# QT2640.net
KiCad netlist of a schematic drawn in EAGLE
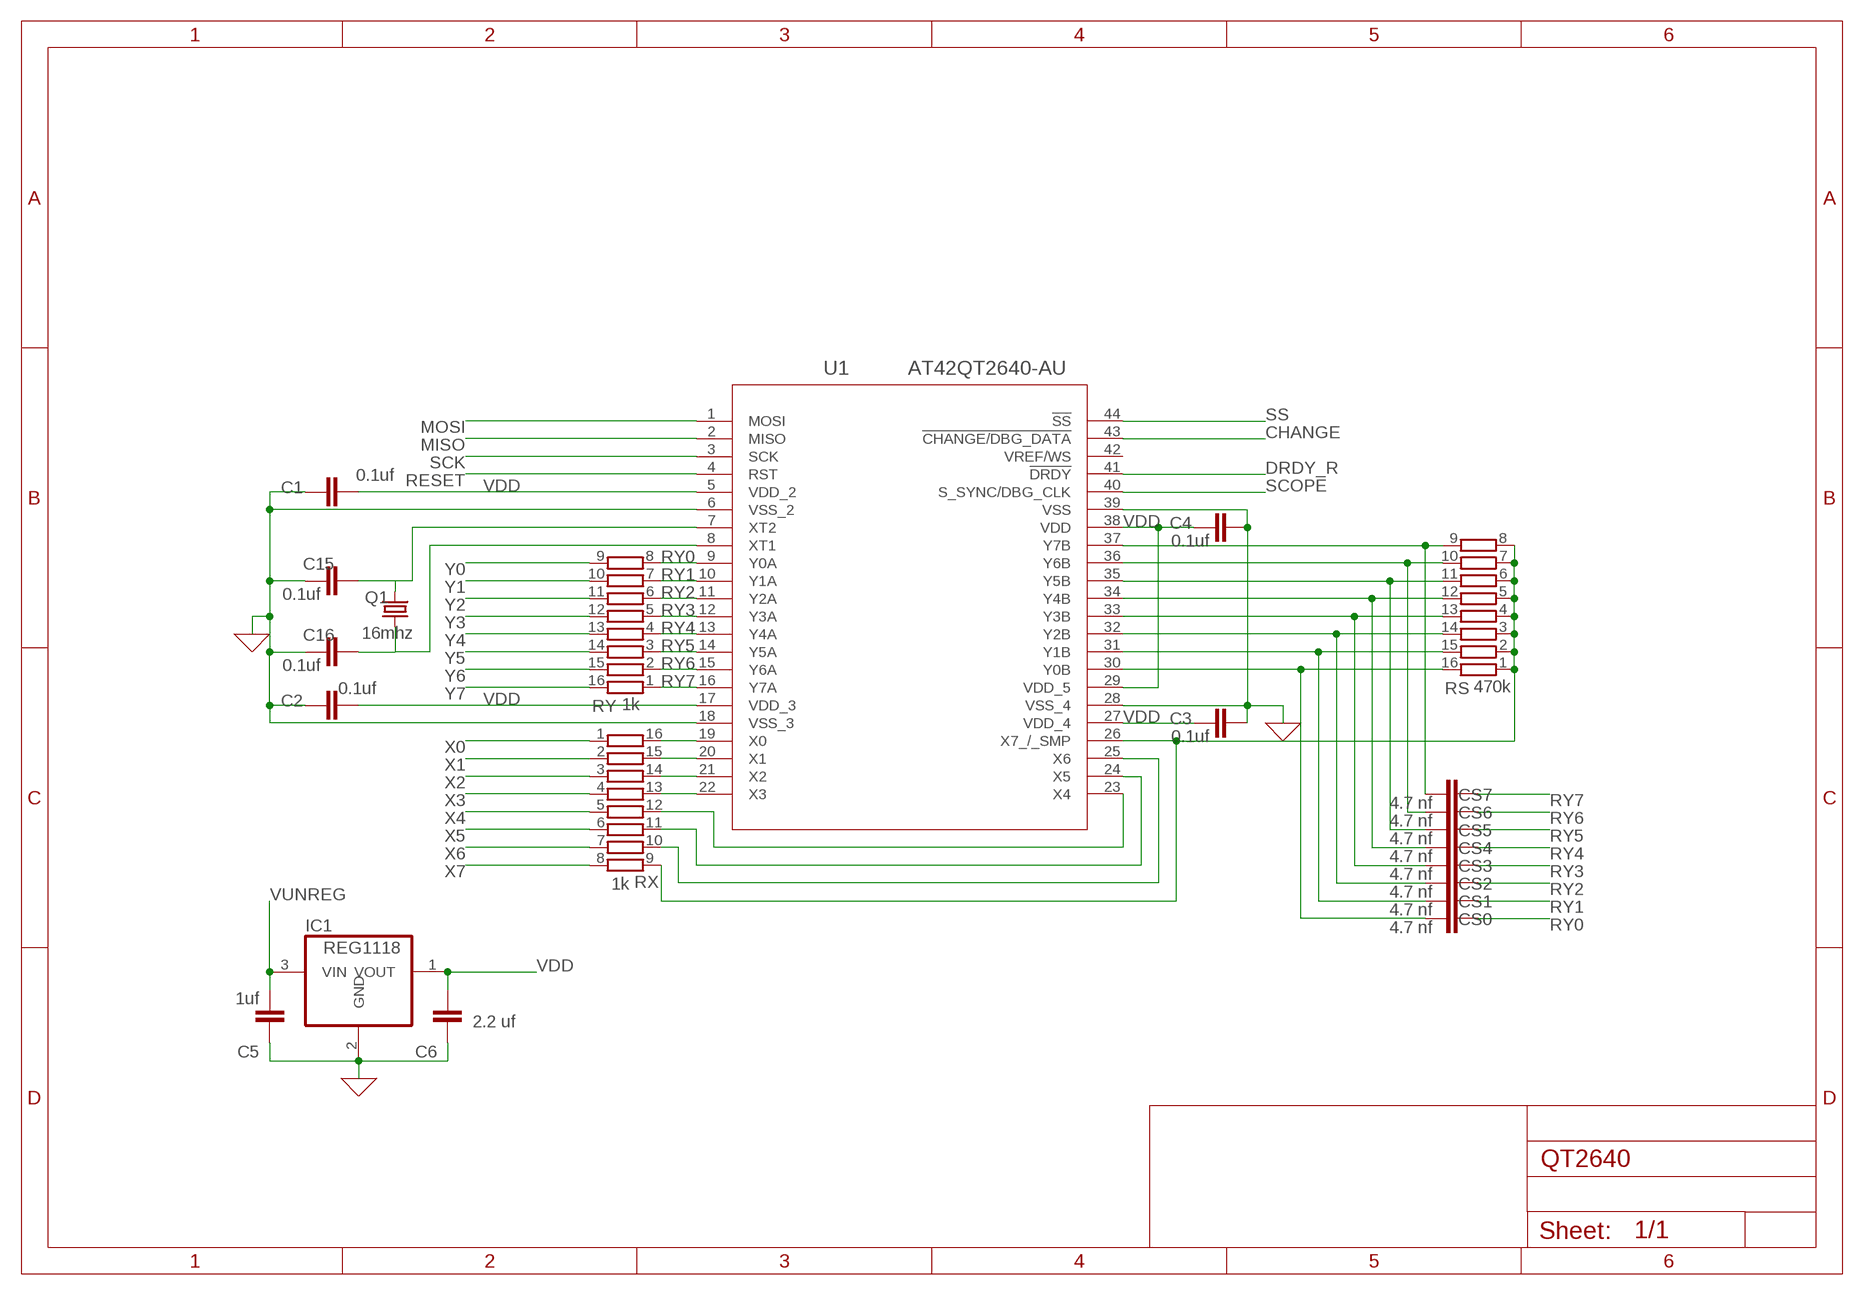
[diagram p0: schematic, sheet 1]

(export (version "E")
  (design (tool "Eeschema 10.0.6"))
  (components
    (comp (ref "C1")
      (value "0.1uf")
      (footprint "eagle-import:C2.5-3")
      (libsource (lib "eagle-import") (part "C2,5-3"))
    )
    (comp (ref "C2")
      (value "0.1uf")
      (footprint "eagle-import:C2.5-3")
      (libsource (lib "eagle-import") (part "C2,5-3"))
    )
    (comp (ref "C3")
      (value "0.1uf")
      (footprint "eagle-import:C2.5-3")
      (libsource (lib "eagle-import") (part "C2,5-3"))
    )
    (comp (ref "C4")
      (value "0.1uf")
      (footprint "eagle-import:C2.5-3")
      (libsource (lib "eagle-import") (part "C2,5-3"))
    )
    (comp (ref "C5")
      (value "1uf")
      (footprint "eagle-import:C2.5-3")
      (libsource (lib "eagle-import") (part "C2,5-3"))
    )
    (comp (ref "C6")
      (value "2.2 uf")
      (footprint "eagle-import:C2.5-3")
      (libsource (lib "eagle-import") (part "C2,5-3"))
    )
    (comp (ref "C15")
      (value "0.1uf")
      (footprint "eagle-import:C2.5-3")
      (libsource (lib "eagle-import") (part "C2,5-3"))
    )
    (comp (ref "C16")
      (value "0.1uf")
      (footprint "eagle-import:C2.5-3")
      (libsource (lib "eagle-import") (part "C2,5-3"))
    )
    (comp (ref "CS0")
      (value "4.7 nf")
      (footprint "eagle-import:C2.5-3")
      (libsource (lib "eagle-import") (part "C2,5-3"))
    )
    (comp (ref "CS1")
      (value "4.7 nf")
      (footprint "eagle-import:C2.5-3")
      (libsource (lib "eagle-import") (part "C2,5-3"))
    )
    (comp (ref "CS2")
      (value "4.7 nf")
      (footprint "eagle-import:C2.5-3")
      (libsource (lib "eagle-import") (part "C2,5-3"))
    )
    (comp (ref "CS3")
      (value "4.7 nf")
      (footprint "eagle-import:C2.5-3")
      (libsource (lib "eagle-import") (part "C2,5-3"))
    )
    (comp (ref "CS4")
      (value "4.7 nf")
      (footprint "eagle-import:C2.5-3")
      (libsource (lib "eagle-import") (part "C2,5-3"))
    )
    (comp (ref "CS5")
      (value "4.7 nf")
      (footprint "eagle-import:C2.5-3")
      (libsource (lib "eagle-import") (part "C2,5-3"))
    )
    (comp (ref "CS6")
      (value "4.7 nf")
      (footprint "eagle-import:C2.5-3")
      (libsource (lib "eagle-import") (part "C2,5-3"))
    )
    (comp (ref "CS7")
      (value "4.7 nf")
      (footprint "eagle-import:C2.5-3")
      (libsource (lib "eagle-import") (part "C2,5-3"))
    )
    (comp (ref "IC1")
      (value "REG1118")
      (footprint "eagle-import:SOT223")
      (fields (field (name "MPN") "REG1118-2.85/2K5G4"))
      (libsource (lib "eagle-import") (part "REG1118"))
    )
    (comp (ref "Q1")
      (value "16mhz")
      (footprint "eagle-import:CSM-7X-DU")
      (libsource (lib "eagle-import") (part "CSM-7X-DU"))
    )
    (comp (ref "RS")
      (value "470k")
      (footprint "eagle-import:4816P")
      (fields (field (name "MF") "BOURNS, INC.") (field (name "MPN") "4816P-T01-684LF"))
      (libsource (lib "eagle-import") (part "4816P-T01"))
    )
    (comp (ref "RX")
      (value "1k")
      (footprint "eagle-import:4816P")
      (fields (field (name "MF") "BOURNS, INC.") (field (name "MPN") "4816P-T01-684LF"))
      (libsource (lib "eagle-import") (part "4816P-T01"))
    )
    (comp (ref "RY")
      (value "1k")
      (footprint "eagle-import:4816P")
      (fields (field (name "MF") "BOURNS, INC.") (field (name "MPN") "4816P-T01-684LF"))
      (libsource (lib "eagle-import") (part "4816P-T01"))
    )
    (comp (ref "U1")
      (value "AT42QT2640-AU")
      (footprint "eagle-import:TQFP44_10X10MC")
      (fields (field (name "COPYRIGHT") "Copyright (C) 2018 Accelerated Designs. All rights reserved"))
      (libsource (lib "eagle-import") (part "AT42QT2640-AU"))
    )
  )
  (nets
    (net (code "1") (name "/CHANGE") (class "Default")
      (node (ref "U1") (pin "43") (pinfunction "~{CHANGE/DBG_DATA}_43") (pintype "passive"))
    )
    (net (code "2") (name "/DRDY_R") (class "Default")
      (node (ref "U1") (pin "41") (pinfunction "~{DRDY}_41") (pintype "passive"))
    )
    (net (code "3") (name "/MISO") (class "Default")
      (node (ref "U1") (pin "2") (pinfunction "MISO_2") (pintype "passive"))
    )
    (net (code "4") (name "/MOSI") (class "Default")
      (node (ref "U1") (pin "1") (pinfunction "MOSI_1") (pintype "passive"))
    )
    (net (code "5") (name "/RESET") (class "Default")
      (node (ref "U1") (pin "4") (pinfunction "RST_4") (pintype "passive"))
    )
    (net (code "6") (name "/RY0") (class "Default")
      (node (ref "CS0") (pin "2") (pinfunction "2_2") (pintype "passive"))
      (node (ref "RY") (pin "8") (pinfunction "8_8") (pintype "passive"))
      (node (ref "U1") (pin "9") (pinfunction "Y0A_9") (pintype "bidirectional"))
    )
    (net (code "7") (name "/RY1") (class "Default")
      (node (ref "CS1") (pin "2") (pinfunction "2_2") (pintype "passive"))
      (node (ref "RY") (pin "7") (pinfunction "7_7") (pintype "passive"))
      (node (ref "U1") (pin "10") (pinfunction "Y1A_10") (pintype "bidirectional"))
    )
    (net (code "8") (name "/RY2") (class "Default")
      (node (ref "CS2") (pin "2") (pinfunction "2_2") (pintype "passive"))
      (node (ref "RY") (pin "6") (pinfunction "6_6") (pintype "passive"))
      (node (ref "U1") (pin "11") (pinfunction "Y2A_11") (pintype "bidirectional"))
    )
    (net (code "9") (name "/RY3") (class "Default")
      (node (ref "CS3") (pin "2") (pinfunction "2_2") (pintype "passive"))
      (node (ref "RY") (pin "5") (pinfunction "5_5") (pintype "passive"))
      (node (ref "U1") (pin "12") (pinfunction "Y3A_12") (pintype "bidirectional"))
    )
    (net (code "10") (name "/RY4") (class "Default")
      (node (ref "CS4") (pin "2") (pinfunction "2_2") (pintype "passive"))
      (node (ref "RY") (pin "4") (pinfunction "4_4") (pintype "passive"))
      (node (ref "U1") (pin "13") (pinfunction "Y4A_13") (pintype "bidirectional"))
    )
    (net (code "11") (name "/RY5") (class "Default")
      (node (ref "CS5") (pin "2") (pinfunction "2_2") (pintype "passive"))
      (node (ref "RY") (pin "3") (pinfunction "3_3") (pintype "passive"))
      (node (ref "U1") (pin "14") (pinfunction "Y5A_14") (pintype "bidirectional"))
    )
    (net (code "12") (name "/RY6") (class "Default")
      (node (ref "CS6") (pin "2") (pinfunction "2_2") (pintype "passive"))
      (node (ref "RY") (pin "2") (pinfunction "2_2") (pintype "passive"))
      (node (ref "U1") (pin "15") (pinfunction "Y6A_15") (pintype "bidirectional"))
    )
    (net (code "13") (name "/RY7") (class "Default")
      (node (ref "CS7") (pin "2") (pinfunction "2_2") (pintype "passive"))
      (node (ref "RY") (pin "1") (pinfunction "1_1") (pintype "passive"))
      (node (ref "U1") (pin "16") (pinfunction "Y7A_16") (pintype "bidirectional"))
    )
    (net (code "14") (name "/SCK") (class "Default")
      (node (ref "U1") (pin "3") (pinfunction "SCK_3") (pintype "passive"))
    )
    (net (code "15") (name "/SCOPE") (class "Default")
      (node (ref "U1") (pin "40") (pinfunction "S_SYNC/DBG_CLK_40") (pintype "passive"))
    )
    (net (code "16") (name "/SS") (class "Default")
      (node (ref "U1") (pin "44") (pinfunction "~{SS}_44") (pintype "passive"))
    )
    (net (code "17") (name "/VDD") (class "Default")
      (node (ref "C1") (pin "2") (pinfunction "2_2") (pintype "passive"))
      (node (ref "C2") (pin "2") (pinfunction "2_2") (pintype "passive"))
      (node (ref "C3") (pin "1") (pinfunction "1_1") (pintype "passive"))
      (node (ref "C4") (pin "1") (pinfunction "1_1") (pintype "passive"))
      (node (ref "C6") (pin "2") (pinfunction "2_2") (pintype "passive"))
      (node (ref "IC1") (pin "1") (pinfunction "VOUT_1") (pintype "output"))
      (node (ref "U1") (pin "17") (pinfunction "VDD_3_17") (pintype "power_in"))
      (node (ref "U1") (pin "27") (pinfunction "VDD_4_27") (pintype "power_in"))
      (node (ref "U1") (pin "29") (pinfunction "VDD_5_29") (pintype "power_in"))
      (node (ref "U1") (pin "38") (pinfunction "VDD_38") (pintype "power_in"))
      (node (ref "U1") (pin "5") (pinfunction "VDD_2_5") (pintype "power_in"))
    )
    (net (code "18") (name "/VREF{slash}WS") (class "Default")
      (node (ref "U1") (pin "42") (pinfunction "VREF/WS_42") (pintype "power_in"))
    )
    (net (code "19") (name "/VUNREG") (class "Default")
      (node (ref "C5") (pin "2") (pinfunction "2_2") (pintype "passive"))
      (node (ref "IC1") (pin "3") (pinfunction "VIN_3") (pintype "input"))
    )
    (net (code "20") (name "/X0") (class "Default")
      (node (ref "RX") (pin "1") (pinfunction "1_1") (pintype "passive"))
    )
    (net (code "21") (name "/X1") (class "Default")
      (node (ref "RX") (pin "2") (pinfunction "2_2") (pintype "passive"))
    )
    (net (code "22") (name "/X2") (class "Default")
      (node (ref "RX") (pin "3") (pinfunction "3_3") (pintype "passive"))
    )
    (net (code "23") (name "/X3") (class "Default")
      (node (ref "RX") (pin "4") (pinfunction "4_4") (pintype "passive"))
    )
    (net (code "24") (name "/X4") (class "Default")
      (node (ref "RX") (pin "5") (pinfunction "5_5") (pintype "passive"))
    )
    (net (code "25") (name "/X5") (class "Default")
      (node (ref "RX") (pin "6") (pinfunction "6_6") (pintype "passive"))
    )
    (net (code "26") (name "/X6") (class "Default")
      (node (ref "RX") (pin "7") (pinfunction "7_7") (pintype "passive"))
    )
    (net (code "27") (name "/X7") (class "Default")
      (node (ref "RX") (pin "8") (pinfunction "8_8") (pintype "passive"))
    )
    (net (code "28") (name "/Y0") (class "Default")
      (node (ref "RY") (pin "9") (pinfunction "9_9") (pintype "passive"))
    )
    (net (code "29") (name "/Y1") (class "Default")
      (node (ref "RY") (pin "10") (pinfunction "10_10") (pintype "passive"))
    )
    (net (code "30") (name "/Y2") (class "Default")
      (node (ref "RY") (pin "11") (pinfunction "11_11") (pintype "passive"))
    )
    (net (code "31") (name "/Y3") (class "Default")
      (node (ref "RY") (pin "12") (pinfunction "12_12") (pintype "passive"))
    )
    (net (code "32") (name "/Y4") (class "Default")
      (node (ref "RY") (pin "13") (pinfunction "13_13") (pintype "passive"))
    )
    (net (code "33") (name "/Y5") (class "Default")
      (node (ref "RY") (pin "14") (pinfunction "14_14") (pintype "passive"))
    )
    (net (code "34") (name "/Y6") (class "Default")
      (node (ref "RY") (pin "15") (pinfunction "15_15") (pintype "passive"))
    )
    (net (code "35") (name "/Y7") (class "Default")
      (node (ref "RY") (pin "16") (pinfunction "16_16") (pintype "passive"))
    )
    (net (code "36") (name "GND") (class "Default")
      (node (ref "C1") (pin "1") (pinfunction "1_1") (pintype "passive"))
      (node (ref "C15") (pin "1") (pinfunction "1_1") (pintype "passive"))
      (node (ref "C16") (pin "1") (pinfunction "1_1") (pintype "passive"))
      (node (ref "C2") (pin "1") (pinfunction "1_1") (pintype "passive"))
      (node (ref "C3") (pin "2") (pinfunction "2_2") (pintype "passive"))
      (node (ref "C4") (pin "2") (pinfunction "2_2") (pintype "passive"))
      (node (ref "C5") (pin "1") (pinfunction "1_1") (pintype "passive"))
      (node (ref "C6") (pin "1") (pinfunction "1_1") (pintype "passive"))
      (node (ref "IC1") (pin "2") (pinfunction "GND_2") (pintype "power_in"))
      (node (ref "U1") (pin "18") (pinfunction "VSS_3_18") (pintype "passive"))
      (node (ref "U1") (pin "28") (pinfunction "VSS_4_28") (pintype "passive"))
      (node (ref "U1") (pin "39") (pinfunction "VSS_39") (pintype "passive"))
      (node (ref "U1") (pin "6") (pinfunction "VSS_2_6") (pintype "passive"))
    )
    (net (code "37") (name "Net-(U1-X0)") (class "Default")
      (node (ref "RX") (pin "16") (pinfunction "16_16") (pintype "passive"))
      (node (ref "U1") (pin "19") (pinfunction "X0_19") (pintype "bidirectional"))
    )
    (net (code "38") (name "Net-(U1-X1)") (class "Default")
      (node (ref "RX") (pin "15") (pinfunction "15_15") (pintype "passive"))
      (node (ref "U1") (pin "20") (pinfunction "X1_20") (pintype "bidirectional"))
    )
    (net (code "39") (name "Net-(U1-X2)") (class "Default")
      (node (ref "RX") (pin "14") (pinfunction "14_14") (pintype "passive"))
      (node (ref "U1") (pin "21") (pinfunction "X2_21") (pintype "bidirectional"))
    )
    (net (code "40") (name "Net-(U1-X3)") (class "Default")
      (node (ref "RX") (pin "13") (pinfunction "13_13") (pintype "passive"))
      (node (ref "U1") (pin "22") (pinfunction "X3_22") (pintype "bidirectional"))
    )
    (net (code "41") (name "Net-(U1-X4)") (class "Default")
      (node (ref "RX") (pin "12") (pinfunction "12_12") (pintype "passive"))
      (node (ref "U1") (pin "23") (pinfunction "X4_23") (pintype "bidirectional"))
    )
    (net (code "42") (name "Net-(U1-X5)") (class "Default")
      (node (ref "RX") (pin "11") (pinfunction "11_11") (pintype "passive"))
      (node (ref "U1") (pin "24") (pinfunction "X5_24") (pintype "bidirectional"))
    )
    (net (code "43") (name "Net-(U1-X6)") (class "Default")
      (node (ref "RX") (pin "10") (pinfunction "10_10") (pintype "passive"))
      (node (ref "U1") (pin "25") (pinfunction "X6_25") (pintype "bidirectional"))
    )
    (net (code "44") (name "Net-(U1-X7_{slash}_SMP)") (class "Default")
      (node (ref "RS") (pin "1") (pinfunction "1_1") (pintype "passive"))
      (node (ref "RS") (pin "2") (pinfunction "2_2") (pintype "passive"))
      (node (ref "RS") (pin "3") (pinfunction "3_3") (pintype "passive"))
      (node (ref "RS") (pin "4") (pinfunction "4_4") (pintype "passive"))
      (node (ref "RS") (pin "5") (pinfunction "5_5") (pintype "passive"))
      (node (ref "RS") (pin "6") (pinfunction "6_6") (pintype "passive"))
      (node (ref "RS") (pin "7") (pinfunction "7_7") (pintype "passive"))
      (node (ref "RS") (pin "8") (pinfunction "8_8") (pintype "passive"))
      (node (ref "RX") (pin "9") (pinfunction "9_9") (pintype "passive"))
      (node (ref "U1") (pin "26") (pinfunction "X7_/_SMP_26") (pintype "bidirectional"))
    )
    (net (code "45") (name "Net-(U1-XT1)") (class "Default")
      (node (ref "C16") (pin "2") (pinfunction "2_2") (pintype "passive"))
      (node (ref "Q1") (pin "1") (pinfunction "1_1") (pintype "passive"))
      (node (ref "U1") (pin "8") (pinfunction "XT1_8") (pintype "bidirectional"))
    )
    (net (code "46") (name "Net-(U1-XT2)") (class "Default")
      (node (ref "C15") (pin "2") (pinfunction "2_2") (pintype "passive"))
      (node (ref "Q1") (pin "2") (pinfunction "2_2") (pintype "passive"))
      (node (ref "U1") (pin "7") (pinfunction "XT2_7") (pintype "bidirectional"))
    )
    (net (code "47") (name "Net-(U1-Y0B)") (class "Default")
      (node (ref "CS0") (pin "1") (pinfunction "1_1") (pintype "passive"))
      (node (ref "RS") (pin "16") (pinfunction "16_16") (pintype "passive"))
      (node (ref "U1") (pin "30") (pinfunction "Y0B_30") (pintype "bidirectional"))
    )
    (net (code "48") (name "Net-(U1-Y1B)") (class "Default")
      (node (ref "CS1") (pin "1") (pinfunction "1_1") (pintype "passive"))
      (node (ref "RS") (pin "15") (pinfunction "15_15") (pintype "passive"))
      (node (ref "U1") (pin "31") (pinfunction "Y1B_31") (pintype "bidirectional"))
    )
    (net (code "49") (name "Net-(U1-Y2B)") (class "Default")
      (node (ref "CS2") (pin "1") (pinfunction "1_1") (pintype "passive"))
      (node (ref "RS") (pin "14") (pinfunction "14_14") (pintype "passive"))
      (node (ref "U1") (pin "32") (pinfunction "Y2B_32") (pintype "bidirectional"))
    )
    (net (code "50") (name "Net-(U1-Y3B)") (class "Default")
      (node (ref "CS3") (pin "1") (pinfunction "1_1") (pintype "passive"))
      (node (ref "RS") (pin "13") (pinfunction "13_13") (pintype "passive"))
      (node (ref "U1") (pin "33") (pinfunction "Y3B_33") (pintype "bidirectional"))
    )
    (net (code "51") (name "Net-(U1-Y4B)") (class "Default")
      (node (ref "CS4") (pin "1") (pinfunction "1_1") (pintype "passive"))
      (node (ref "RS") (pin "12") (pinfunction "12_12") (pintype "passive"))
      (node (ref "U1") (pin "34") (pinfunction "Y4B_34") (pintype "bidirectional"))
    )
    (net (code "52") (name "Net-(U1-Y5B)") (class "Default")
      (node (ref "CS5") (pin "1") (pinfunction "1_1") (pintype "passive"))
      (node (ref "RS") (pin "11") (pinfunction "11_11") (pintype "passive"))
      (node (ref "U1") (pin "35") (pinfunction "Y5B_35") (pintype "bidirectional"))
    )
    (net (code "53") (name "Net-(U1-Y6B)") (class "Default")
      (node (ref "CS6") (pin "1") (pinfunction "1_1") (pintype "passive"))
      (node (ref "RS") (pin "10") (pinfunction "10_10") (pintype "passive"))
      (node (ref "U1") (pin "36") (pinfunction "Y6B_36") (pintype "bidirectional"))
    )
    (net (code "54") (name "Net-(U1-Y7B)") (class "Default")
      (node (ref "CS7") (pin "1") (pinfunction "1_1") (pintype "passive"))
      (node (ref "RS") (pin "9") (pinfunction "9_9") (pintype "passive"))
      (node (ref "U1") (pin "37") (pinfunction "Y7B_37") (pintype "passive"))
    )
  )
)
